# Sheet1.net
KiCad netlist of a schematic drawn in Altium Designer
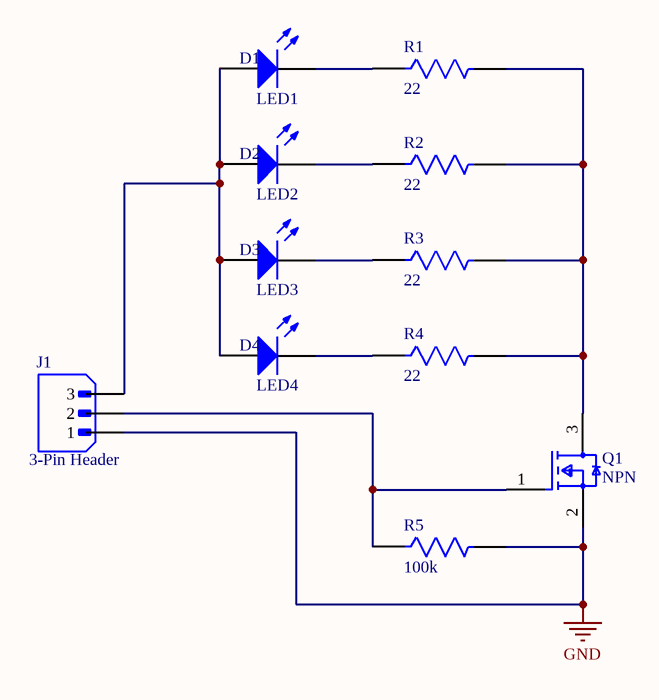
[diagram p0: Sheet1.SchDoc]

(export (version "E")
  (design (tool "Eeschema 10.0.6"))
  (components
    (comp (ref "D1")
      (value "LED1")
      (footprint "LUMD-L128_V")
      (fields (field (name "VOLTAGE") "9 V") (field (name "MANUFACTURER") "Lumileds"))
      (libsource (lib "Altium Content Vault") (part "LED-KA-2"))
    )
    (comp (ref "D2")
      (value "LED2")
      (footprint "LUMD-L128_V")
      (fields (field (name "VOLTAGE") "9 V") (field (name "MANUFACTURER") "Lumileds"))
      (libsource (lib "Altium Content Vault") (part "LED-KA-2"))
    )
    (comp (ref "D3")
      (value "LED3")
      (footprint "LUMD-L128_V")
      (fields (field (name "VOLTAGE") "9 V") (field (name "MANUFACTURER") "Lumileds"))
      (libsource (lib "Altium Content Vault") (part "LED-KA-2"))
    )
    (comp (ref "D4")
      (value "LED4")
      (footprint "LUMD-L128_V")
      (fields (field (name "VOLTAGE") "9 V") (field (name "MANUFACTURER") "Lumileds"))
      (libsource (lib "Altium Content Vault") (part "LED-KA-2"))
    )
    (comp (ref "J1")
      (value "3-Pin Header")
      (footprint "JST_B3B-XH-A")
      (description "Connector Header Through Hole 3 position 0.098 (2.50mm)")
      (fields (field (name "MF") "JST Sales") (field (name "MP") "B3B-XH-A"))
      (libsource (lib "B3B-XH-A (1)") (part "B3B-XH-A"))
    )
    (comp (ref "Q1")
      (value "NPN")
      (footprint "FP-SOT23-MFG")
      (description "MOSFET N-CH 30V 5.7A SOT23")
      (libsource (lib "Altium Content Vault") (part "0a9ea7c96deaaede766a5b531c28de0"))
    )
    (comp (ref "R1")
      (value "22")
      (footprint "FP-SR1206-MFG")
      (description "RES 22 OHM 1% 1/2W 1206")
      (fields (field (name "TOLERANCE") "0.01") (field (name "MANUFACTURER PART NUMBER") "SR1206FR-7W22RL"))
      (libsource (lib "Altium Content Vault") (part "1029c3af85768c4190bb7ad29bc67b5"))
    )
    (comp (ref "R2")
      (value "22")
      (footprint "FP-SR1206-MFG")
      (description "RES 22 OHM 1% 1/2W 1206")
      (fields (field (name "TOLERANCE") "0.01") (field (name "MANUFACTURER PART NUMBER") "SR1206FR-7W22RL"))
      (libsource (lib "Altium Content Vault") (part "1029c3af85768c4190bb7ad29bc67b5"))
    )
    (comp (ref "R3")
      (value "22")
      (footprint "FP-SR1206-MFG")
      (description "RES 22 OHM 1% 1/2W 1206")
      (fields (field (name "TOLERANCE") "0.01") (field (name "MANUFACTURER PART NUMBER") "SR1206FR-7W22RL"))
      (libsource (lib "Altium Content Vault") (part "1029c3af85768c4190bb7ad29bc67b5"))
    )
    (comp (ref "R4")
      (value "22")
      (footprint "FP-SR1206-MFG")
      (description "RES 22 OHM 1% 1/2W 1206")
      (fields (field (name "TOLERANCE") "0.01") (field (name "MANUFACTURER PART NUMBER") "SR1206FR-7W22RL"))
      (libsource (lib "Altium Content Vault") (part "1029c3af85768c4190bb7ad29bc67b5"))
    )
    (comp (ref "R5")
      (value "100k")
      (footprint "FP-CRGP0603-IPC_C")
      (description "CRGP 0603 100K 1%")
      (fields
        (field (name "MANUFACTURER") "TE")
        (field (name "OCTOPART") "https://octopart.com/crgp0603f100k-te+connectivity-91018719")
      )
      (libsource (lib "Altium Content Vault") (part "1029c3af85768c4190bb7ad29bc67b5"))
    )
  )
  (nets
    (net (code "1") (name "GND") (class "Default")
      (node (ref "J1") (pin "1") (pinfunction "1_1") (pintype "passive"))
      (node (ref "Q1") (pin "2") (pinfunction "S_2") (pintype "passive"))
      (node (ref "R5") (pin "2") (pinfunction "2_2") (pintype "passive"))
    )
    (net (code "2") (name "Net-(D1-A)") (class "Default")
      (node (ref "D1") (pin "2") (pinfunction "A_2") (pintype "passive"))
      (node (ref "D2") (pin "2") (pinfunction "A_2") (pintype "passive"))
      (node (ref "D3") (pin "2") (pinfunction "A_2") (pintype "passive"))
      (node (ref "D4") (pin "2") (pinfunction "A_2") (pintype "passive"))
      (node (ref "J1") (pin "3") (pinfunction "3_3") (pintype "passive"))
    )
    (net (code "3") (name "Net-(D1-K)") (class "Default")
      (node (ref "D1") (pin "1") (pinfunction "K_1") (pintype "passive"))
      (node (ref "R1") (pin "1") (pinfunction "1_1") (pintype "passive"))
    )
    (net (code "4") (name "Net-(D2-K)") (class "Default")
      (node (ref "D2") (pin "1") (pinfunction "K_1") (pintype "passive"))
      (node (ref "R2") (pin "1") (pinfunction "1_1") (pintype "passive"))
    )
    (net (code "5") (name "Net-(D3-K)") (class "Default")
      (node (ref "D3") (pin "1") (pinfunction "K_1") (pintype "passive"))
      (node (ref "R3") (pin "1") (pinfunction "1_1") (pintype "passive"))
    )
    (net (code "6") (name "Net-(D4-K)") (class "Default")
      (node (ref "D4") (pin "1") (pinfunction "K_1") (pintype "passive"))
      (node (ref "R4") (pin "1") (pinfunction "1_1") (pintype "passive"))
    )
    (net (code "7") (name "Net-(Q1-D)") (class "Default")
      (node (ref "Q1") (pin "3") (pinfunction "D_3") (pintype "passive"))
      (node (ref "R1") (pin "2") (pinfunction "2_2") (pintype "passive"))
      (node (ref "R2") (pin "2") (pinfunction "2_2") (pintype "passive"))
      (node (ref "R3") (pin "2") (pinfunction "2_2") (pintype "passive"))
      (node (ref "R4") (pin "2") (pinfunction "2_2") (pintype "passive"))
    )
    (net (code "8") (name "Net-(Q1-G)") (class "Default")
      (node (ref "J1") (pin "2") (pinfunction "2_2") (pintype "passive"))
      (node (ref "Q1") (pin "1") (pinfunction "G_1") (pintype "passive"))
      (node (ref "R5") (pin "1") (pinfunction "1_1") (pintype "passive"))
    )
  )
)
